# JTAG_Adapter.net
KiCad netlist of a schematic drawn in Altium Designer
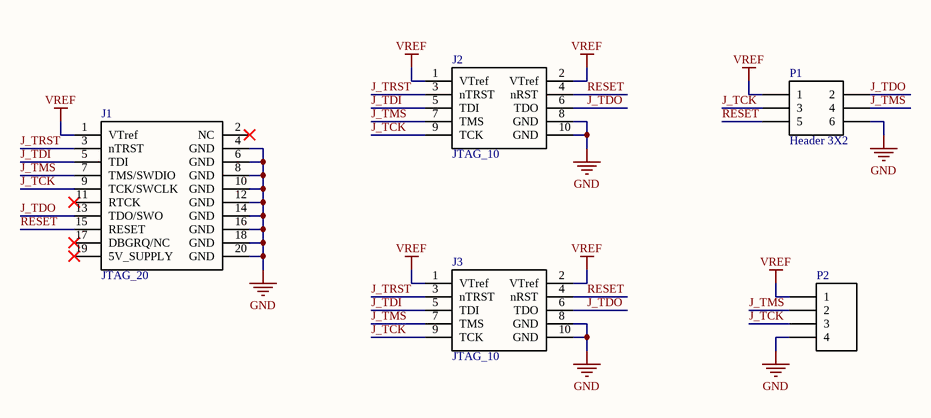
[diagram p0: JTAG_Adapter.SchDoc]

(export (version "E")
  (design (tool "Eeschema 10.0.6"))
  (components
    (comp (ref "J1") (value "JTAG_20") (footprint "JTAG_20") (libsource (lib "Connectors") (part "JTAG_20")))
    (comp (ref "J2") (value "JTAG_10") (footprint "JTAG_10") (libsource (lib "Connectors") (part "JTAG_10")))
    (comp (ref "J3") (value "JTAG_10") (footprint "JTAG_10") (libsource (lib "Connectors") (part "JTAG_10")))
    (comp (ref "P1")
      (value "Header 3X2")
      (footprint "DIP6-2.00-BH2")
      (description "Header, 3-Pin, Dual row")
      (libsource (lib "Connectors") (part "Header 3X2"))
    )
    (comp (ref "P2")
      (value "Header 4")
      (footprint "XH2.54_4P")
      (description "Header, 4-Pin")
      (fields (field (name "PUBLISHER") "Altium Limited"))
      (libsource (lib "Connectors") (part "Header 4"))
    )
  )
  (nets
    (net (code "1") (name "/J_TCK") (class "Default")
      (node (ref "J1") (pin "9") (pinfunction "TCK/SWCLK_9") (pintype "passive"))
      (node (ref "J2") (pin "9") (pinfunction "TCK_9") (pintype "passive"))
      (node (ref "J3") (pin "9") (pinfunction "TCK_9") (pintype "passive"))
      (node (ref "P1") (pin "3") (pinfunction "3_3") (pintype "passive"))
      (node (ref "P2") (pin "3") (pinfunction "3_3") (pintype "passive"))
    )
    (net (code "2") (name "/J_TDI") (class "Default")
      (node (ref "J1") (pin "5") (pinfunction "TDI_5") (pintype "passive"))
      (node (ref "J2") (pin "5") (pinfunction "TDI_5") (pintype "passive"))
      (node (ref "J3") (pin "5") (pinfunction "TDI_5") (pintype "passive"))
    )
    (net (code "3") (name "/J_TDO") (class "Default")
      (node (ref "J1") (pin "13") (pinfunction "TDO/SWO_13") (pintype "passive"))
      (node (ref "J2") (pin "6") (pinfunction "TDO_6") (pintype "passive"))
      (node (ref "J3") (pin "6") (pinfunction "TDO_6") (pintype "passive"))
      (node (ref "P1") (pin "2") (pinfunction "2_2") (pintype "passive"))
    )
    (net (code "4") (name "/J_TMS") (class "Default")
      (node (ref "J1") (pin "7") (pinfunction "TMS/SWDIO_7") (pintype "passive"))
      (node (ref "J2") (pin "7") (pinfunction "TMS_7") (pintype "passive"))
      (node (ref "J3") (pin "7") (pinfunction "TMS_7") (pintype "passive"))
      (node (ref "P1") (pin "4") (pinfunction "4_4") (pintype "passive"))
      (node (ref "P2") (pin "2") (pinfunction "2_2") (pintype "passive"))
    )
    (net (code "5") (name "/J_TRST") (class "Default")
      (node (ref "J1") (pin "3") (pinfunction "nTRST_3") (pintype "passive"))
      (node (ref "J2") (pin "3") (pinfunction "nTRST_3") (pintype "passive"))
      (node (ref "J3") (pin "3") (pinfunction "nTRST_3") (pintype "passive"))
    )
    (net (code "6") (name "/RESET") (class "Default")
      (node (ref "J1") (pin "15") (pinfunction "RESET_15") (pintype "passive"))
      (node (ref "J2") (pin "4") (pinfunction "nRST_4") (pintype "passive"))
      (node (ref "J3") (pin "4") (pinfunction "nRST_4") (pintype "passive"))
      (node (ref "P1") (pin "5") (pinfunction "5_5") (pintype "passive"))
    )
    (net (code "7") (name "GND") (class "Default")
      (node (ref "J1") (pin "10") (pinfunction "GND_10") (pintype "passive"))
      (node (ref "J1") (pin "12") (pinfunction "GND_12") (pintype "passive"))
      (node (ref "J1") (pin "14") (pinfunction "GND_14") (pintype "passive"))
      (node (ref "J1") (pin "16") (pinfunction "GND_16") (pintype "passive"))
      (node (ref "J1") (pin "18") (pinfunction "GND_18") (pintype "passive"))
      (node (ref "J1") (pin "20") (pinfunction "GND_20") (pintype "passive"))
      (node (ref "J1") (pin "4") (pinfunction "GND_4") (pintype "passive"))
      (node (ref "J1") (pin "6") (pinfunction "GND_6") (pintype "passive"))
      (node (ref "J1") (pin "8") (pinfunction "GND_8") (pintype "passive"))
      (node (ref "J2") (pin "10") (pinfunction "GND_10") (pintype "passive"))
      (node (ref "J2") (pin "8") (pinfunction "GND_8") (pintype "passive"))
      (node (ref "J3") (pin "10") (pinfunction "GND_10") (pintype "passive"))
      (node (ref "J3") (pin "8") (pinfunction "GND_8") (pintype "passive"))
      (node (ref "P1") (pin "6") (pinfunction "6_6") (pintype "passive"))
      (node (ref "P2") (pin "4") (pinfunction "4_4") (pintype "passive"))
    )
    (net (code "8") (name "VREF") (class "Default")
      (node (ref "J1") (pin "1") (pinfunction "VTref_1") (pintype "passive"))
      (node (ref "J2") (pin "1") (pinfunction "VTref_1") (pintype "passive"))
      (node (ref "J2") (pin "2") (pinfunction "VTref_2") (pintype "passive"))
      (node (ref "J3") (pin "1") (pinfunction "VTref_1") (pintype "passive"))
      (node (ref "J3") (pin "2") (pinfunction "VTref_2") (pintype "passive"))
      (node (ref "P1") (pin "1") (pinfunction "1_1") (pintype "passive"))
      (node (ref "P2") (pin "1") (pinfunction "1_1") (pintype "passive"))
    )
    (net (code "9") (name "unconnected-(J1-5V_SUPPLY-Pad19)") (class "Default")
      (node (ref "J1") (pin "19") (pinfunction "5V_SUPPLY_19") (pintype "passive+no_connect"))
    )
    (net (code "10") (name "unconnected-(J1-DBGRQ{slash}NC-Pad17)") (class "Default")
      (node (ref "J1") (pin "17") (pinfunction "DBGRQ/NC_17") (pintype "passive+no_connect"))
    )
    (net (code "11") (name "unconnected-(J1-NC-Pad2)") (class "Default")
      (node (ref "J1") (pin "2") (pinfunction "NC_2") (pintype "passive+no_connect"))
    )
    (net (code "12") (name "unconnected-(J1-RTCK-Pad11)") (class "Default")
      (node (ref "J1") (pin "11") (pinfunction "RTCK_11") (pintype "passive+no_connect"))
    )
  )
)
